# Bluetooth.net
KiCad netlist of a schematic drawn in Altium Designer
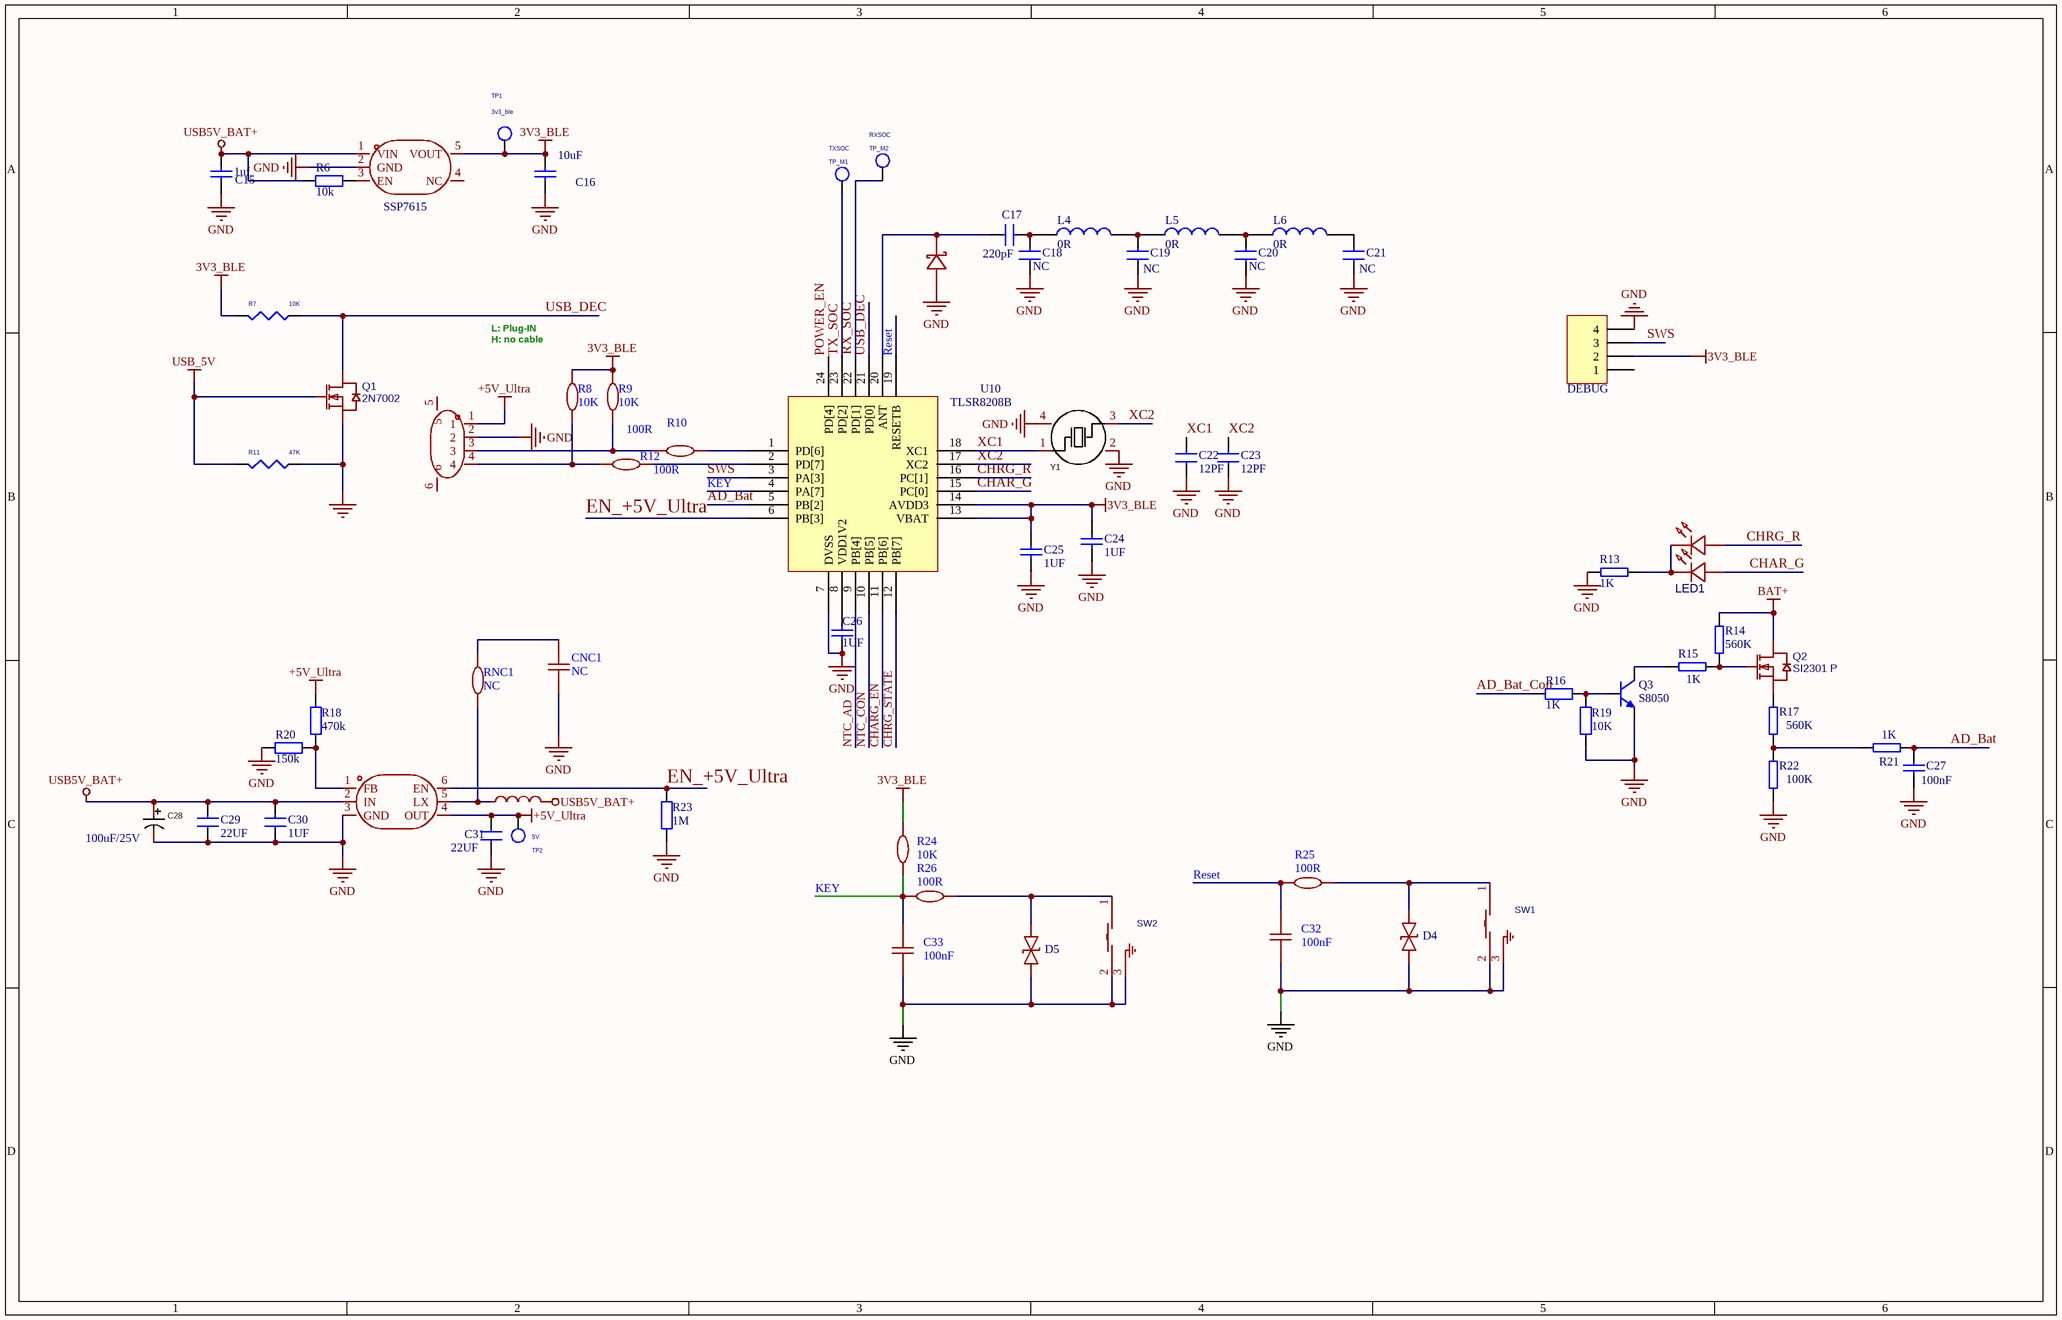
[diagram p0: Bluetooth.SchDoc]

(export (version "E")
  (design (tool "Eeschema 10.0.6"))
  (components
    (comp (ref "C15")
      (value "1uf")
      (footprint "0603_C")
      (description "无极电容")
      (libsource (lib "电容电阻电感保险") (part "Cap1"))
    )
    (comp (ref "C16")
      (value "10uF")
      (footprint "0603_C")
      (description "Capacitor")
      (fields (field (name "PUBLISHER") "Altium Limited"))
      (libsource (lib "*") (part "Cap"))
    )
    (comp (ref "C17")
      (value "220pF")
      (footprint "0402_c")
      (description "Capacitor")
      (libsource (lib "*") (part "CAP"))
    )
    (comp (ref "C18")
      (value "NC")
      (footprint "0402_C")
      (description "Capacitor")
      (libsource (lib "*") (part "CAP"))
    )
    (comp (ref "C19")
      (value "NC")
      (footprint "0402_C")
      (description "Capacitor")
      (libsource (lib "*") (part "CAP"))
    )
    (comp (ref "C20")
      (value "NC")
      (footprint "0402_C")
      (description "Capacitor")
      (libsource (lib "*") (part "CAP"))
    )
    (comp (ref "C21")
      (value "NC")
      (footprint "0402_C")
      (description "Capacitor")
      (libsource (lib "*") (part "CAP"))
    )
    (comp (ref "C22")
      (value "12PF")
      (footprint "0603_c")
      (description "Capacitor")
      (libsource (lib "*") (part "CAP"))
    )
    (comp (ref "C23")
      (value "12PF")
      (footprint "0603_c")
      (description "Capacitor")
      (libsource (lib "*") (part "CAP"))
    )
    (comp (ref "C24") (value "1UF") (footprint "0603_c") (libsource (lib "DIY") (part "CAP")))
    (comp (ref "C25") (value "1UF") (footprint "0603_c") (libsource (lib "DIY") (part "CAP")))
    (comp (ref "C26") (value "1UF") (footprint "0603_c") (libsource (lib "DIY") (part "CAP")))
    (comp (ref "C27") (value "100nF") (footprint "c0402") (libsource (lib "DIY") (part "CAP")))
    (comp (ref "C28")
      (value "100uF/25V")
      (footprint "SMD 6.3*5.4 电解")
      (fields (field (name "MANUFACTURER PART") "RVT1A221M0605"))
      (libsource (lib "altium-import") (part "root_0_RVT1A221M0605_C72494_"))
    )
    (comp (ref "C29")
      (value "22UF")
      (footprint "0805_c")
      (description "Capacitor")
      (libsource (lib "*") (part "CAP"))
    )
    (comp (ref "C30")
      (value "1UF")
      (footprint "0402_c")
      (description "Capacitor")
      (libsource (lib "*") (part "CAP"))
    )
    (comp (ref "C31")
      (value "22UF")
      (footprint "0805_c")
      (description "Capacitor")
      (libsource (lib "*") (part "CAP"))
    )
    (comp (ref "C32")
      (value "100nF")
      (footprint "c0402")
      (libsource (lib "altium-import") (part "root_1_CAP_0603_"))
    )
    (comp (ref "C33")
      (value "100nF")
      (footprint "c0402")
      (libsource (lib "altium-import") (part "root_1_CAP_0603_"))
    )
    (comp (ref "CNC1")
      (value "NC")
      (footprint "c0402")
      (libsource (lib "altium-import") (part "root_1_mirrored_CAP_0603_"))
    )
    (comp (ref "CON4")
      (value "Ultra")
      (footprint "CONN-SMD_4P-P1.25_LT")
      (libsource (lib "altium-import") (part "root_0_mirrored_HC-1.25-4PLT_"))
    )
    (comp (ref "D3")
      (value "SE6V3LHN102T 6.3v单向")
      (footprint "0402-D")
      (libsource (lib "altium-import") (part "root_3_TPNSR05F20NXT5G_"))
    )
    (comp (ref "D4")
      (value "LESD5Z5.0CT1G")
      (footprint "SOD-523_L1.2-W0.8-LS1.6-BI")
      (libsource (lib "altium-import") (part "root_1_LESD5Z5.0CT1G_"))
    )
    (comp (ref "D5")
      (value "LESD5Z5.0CT1G")
      (footprint "SOD-523_L1.2-W0.8-LS1.6-BI")
      (libsource (lib "altium-import") (part "root_1_LESD5Z5.0CT1G_"))
    )
    (comp (ref "L4") (value "0R") (footprint "0402_R") (libsource (lib "*") (part "INDUCTOR")))
    (comp (ref "L5") (value "0R") (footprint "0402_R") (libsource (lib "*") (part "INDUCTOR")))
    (comp (ref "L6") (value "0R") (footprint "0402_R") (libsource (lib "*") (part "INDUCTOR")))
    (comp (ref "L7")
      (value "SLW3012P1R5MST SMD3.0*3.0")
      (footprint "IND-SMD_L3.0-W3.0")
      (libsource (lib "altium-import") (part "root_0_SLW3012P1R5MST_"))
    )
    (comp (ref "LED1")
      (value "*")
      (footprint "LED-SMD_4P-L3.2-W1.6-TL_XL-3216SURUGC")
      (libsource (lib "altium-import") (part "root_0_TJ-S2012SW8TCGLC2R2G-A5_"))
    )
    (comp (ref "P1")
      (value "DEBUG")
      (footprint "SIP4-2.54")
      (description "Header, 4-Pin")
      (fields (field (name "PUBLISHER") "Altium Limited"))
      (libsource (lib "Miscellaneous Connectors") (part "Header 4"))
    )
    (comp (ref "Q1")
      (value "2N7002")
      (footprint "SOT-23")
      (fields
        (field (name "BOM_SUPPLIER PART") "C2890442")
        (field (name "BOM_MANUFACTURER PART") "JMTL3400A")
        (field (name "CONTRIBUTOR") "LCSC")
      )
      (libsource (lib "altium-import") (part "root_0_JMTL3400A_"))
    )
    (comp (ref "Q2")
      (value "SI2301 P")
      (footprint "SOT-23")
      (fields
        (field (name "BOM_SUPPLIER PART") "C2890442")
        (field (name "BOM_MANUFACTURER PART") "JMTL3400A")
        (field (name "CONTRIBUTOR") "LCSC")
      )
      (libsource (lib "") (part "root_0_JMTL3400A__1"))
    )
    (comp (ref "Q3")
      (value "S8050")
      (footprint "SOT-23(SOT-23-3)")
      (description "NPN三极管")
      (libsource (lib "二三极管mos可控硅") (part "NPN_sot23"))
    )
    (comp (ref "R6")
      (value "10k")
      (footprint "R0402")
      (description "Resistor")
      (fields (field (name "PUBLISHER") "Altium Limited"))
      (libsource (lib "") (part "Res2_1"))
    )
    (comp (ref "R7") (value "10K") (footprint "R0402") (libsource (lib "*") (part "R_Dup2")))
    (comp (ref "R8")
      (value "10K")
      (footprint "R0402")
      (libsource (lib "altium-import") (part "root_3_Res_0603_"))
    )
    (comp (ref "R9")
      (value "10K")
      (footprint "R0402")
      (libsource (lib "altium-import") (part "root_3_Res_0603_"))
    )
    (comp (ref "R10")
      (value "100R")
      (footprint "R0402")
      (libsource (lib "altium-import") (part "root_2_Res_0603_"))
    )
    (comp (ref "R11") (value "47K") (footprint "R0402") (libsource (lib "*") (part "R_Dup2")))
    (comp (ref "R12")
      (value "100R")
      (footprint "R0402")
      (libsource (lib "altium-import") (part "root_2_Res_0603_"))
    )
    (comp (ref "R13") (value "1K") (footprint "0603_R") (libsource (lib "DIY") (part "RES")))
    (comp (ref "R14") (value "560K") (footprint "R0402") (libsource (lib "") (part "RES_1")))
    (comp (ref "R15") (value "1K") (footprint "R0402") (libsource (lib "*") (part "RES")))
    (comp (ref "R16")
      (value "1K")
      (footprint "R0402")
      (description "Resistor")
      (fields (field (name "PUBLISHER") "Altium Limited"))
      (libsource (lib "") (part "Res2_3"))
    )
    (comp (ref "R17") (value "560K") (footprint "R0402") (libsource (lib "DIY") (part "RES")))
    (comp (ref "R18")
      (value "470k")
      (footprint "0402_r")
      (description "Resistor")
      (fields (field (name "PUBLISHER") "Altium Limited"))
      (libsource (lib "*") (part "Res2"))
    )
    (comp (ref "R19")
      (value "10K")
      (footprint "R0402")
      (description "Resistor")
      (fields (field (name "PUBLISHER") "Altium Limited"))
      (libsource (lib "") (part "Res2_1"))
    )
    (comp (ref "R20")
      (value "150k")
      (footprint "0402_r")
      (description "Resistor")
      (fields (field (name "PUBLISHER") "Altium Limited"))
      (libsource (lib "") (part "Res2_2"))
    )
    (comp (ref "R21") (value "1K") (footprint "R0402") (libsource (lib "DIY") (part "RES")))
    (comp (ref "R22") (value "100K") (footprint "R0402") (libsource (lib "DIY") (part "RES")))
    (comp (ref "R23")
      (value "1M")
      (footprint "0402_r")
      (description "Resistor")
      (fields (field (name "PUBLISHER") "Altium Limited"))
      (libsource (lib "*") (part "Res2"))
    )
    (comp (ref "R24")
      (value "10K")
      (footprint "R0402")
      (libsource (lib "altium-import") (part "root_1_Res_0603_"))
    )
    (comp (ref "R25")
      (value "100R")
      (footprint "R0402")
      (libsource (lib "altium-import") (part "root_2_Res_0603_"))
    )
    (comp (ref "R26")
      (value "100R")
      (footprint "R0402")
      (libsource (lib "altium-import") (part "root_2_Res_0603_"))
    )
    (comp (ref "RNC1")
      (value "NC")
      (footprint "R0402")
      (libsource (lib "altium-import") (part "root_3_Res_0603_"))
    )
    (comp (ref "SW1")
      (value "Reset")
      (footprint "SMD-KEY-3")
      (libsource (lib "altium-import") (part "root_1_K2-1109SE-I4SW-04_"))
    )
    (comp (ref "SW2")
      (value "OnOff")
      (footprint "SMD-KEY-3")
      (libsource (lib "altium-import") (part "root_1_K2-1109SE-I4SW-04_"))
    )
    (comp (ref "TP1") (value "3v3_ble") (footprint "TP") (libsource (lib "*") (part "T POINT R")))
    (comp (ref "TP2") (value "5V") (footprint "TP") (libsource (lib "*") (part "T POINT R")))
    (comp (ref "TP_M1") (value "TXSOC") (footprint "TP") (libsource (lib "*") (part "T POINT R")))
    (comp (ref "TP_M2") (value "RXSOC") (footprint "TP") (libsource (lib "*") (part "T POINT R")))
    (comp (ref "U2")
      (value "SSP7615")
      (footprint "SOT-23-5")
      (libsource (lib "altium-import") (part "root_0_SSP7615-33M5R_"))
    )
    (comp (ref "U3")
      (value "SY7069ADC")
      (footprint "SOT-23-6")
      (libsource (lib "altium-import") (part "root_0_SY7069ADC_"))
    )
    (comp (ref "U10")
      (value "TLSR8208B")
      (footprint "QFN-24-EP(4*4)")
      (libsource (lib "MyLib") (part "TLSR8208B"))
    )
    (comp (ref "Y1")
      (value "24MHz +-20PPM")
      (footprint "CRYSTAL-SMD_4P-L3.2-W2.5")
      (fields (field (name "MANUFACTURER PART") "TAXM13.56M4RLBCCT2T"))
      (libsource (lib "altium-import") (part "root_0_TAXM13.56M4RLBCCT2T_"))
    )
  )
  (nets
    (net (code "1") (name "+5V_Ultra") (class "Default")
      (node (ref "C31") (pin "2") (pinfunction "2_2") (pintype "passive"))
      (node (ref "CON4") (pin "1") (pinfunction "1_1") (pintype "passive"))
      (node (ref "R18") (pin "2") (pinfunction "2_2") (pintype "passive"))
      (node (ref "TP2") (pin "1") (pinfunction "TP_1") (pintype "passive"))
      (node (ref "U3") (pin "4") (pinfunction "OUT_4") (pintype "passive"))
    )
    (net (code "2") (name "/AD_Bat") (class "Default")
      (node (ref "C27") (pin "2") (pintype "passive"))
      (node (ref "R21") (pin "1") (pinfunction "1_1") (pintype "passive"))
      (node (ref "U10") (pin "5") (pinfunction "PB[2]_5") (pintype "passive"))
    )
    (net (code "3") (name "/AD_Bat_Con") (class "Default")
      (node (ref "R16") (pin "2") (pinfunction "2_2") (pintype "passive"))
    )
    (net (code "4") (name "/CHARG_EN") (class "Default")
      (node (ref "U10") (pin "11") (pinfunction "PB[6]_11") (pintype "passive"))
    )
    (net (code "5") (name "/CHAR_G") (class "Default")
      (node (ref "LED1") (pin "3") (pinfunction "A_3") (pintype "passive"))
      (node (ref "U10") (pin "15") (pinfunction "PC[0]_15") (pintype "passive"))
    )
    (net (code "6") (name "/CHRG_R") (class "Default")
      (node (ref "LED1") (pin "1") (pinfunction "A_1") (pintype "passive"))
      (node (ref "U10") (pin "16") (pinfunction "PC[1]_16") (pintype "passive"))
    )
    (net (code "7") (name "/CHRG_STATE") (class "Default")
      (node (ref "U10") (pin "12") (pinfunction "PB[7]_12") (pintype "passive"))
    )
    (net (code "8") (name "/EN_+5V_Ultra") (class "Default")
      (node (ref "R23") (pin "2") (pinfunction "2_2") (pintype "passive"))
      (node (ref "U10") (pin "6") (pinfunction "PB[3]_6") (pintype "passive"))
      (node (ref "U3") (pin "6") (pinfunction "EN_6") (pintype "passive"))
    )
    (net (code "9") (name "/KEY") (class "Default")
      (node (ref "C33") (pin "2") (pinfunction "2_2") (pintype "passive"))
      (node (ref "R24") (pin "1") (pinfunction "1_1") (pintype "passive"))
      (node (ref "R26") (pin "2") (pinfunction "2_2") (pintype "passive"))
      (node (ref "U10") (pin "4") (pinfunction "PA[7]_4") (pintype "passive"))
    )
    (net (code "10") (name "/NTC_AD") (class "Default")
      (node (ref "U10") (pin "9") (pinfunction "PB[4]_9") (pintype "passive"))
    )
    (net (code "11") (name "/NTC_CON") (class "Default")
      (node (ref "U10") (pin "10") (pinfunction "PB[5]_10") (pintype "passive"))
    )
    (net (code "12") (name "/POWER_EN") (class "Default")
      (node (ref "U10") (pin "24") (pinfunction "PD[4]_24") (pintype "passive"))
    )
    (net (code "13") (name "/RX_SOC") (class "Default")
      (node (ref "TP_M2") (pin "1") (pinfunction "TP_1") (pintype "passive"))
      (node (ref "U10") (pin "22") (pinfunction "PD[1]_22") (pintype "passive"))
    )
    (net (code "14") (name "/Reset") (class "Default")
      (node (ref "C32") (pin "2") (pinfunction "2_2") (pintype "passive"))
      (node (ref "R25") (pin "2") (pinfunction "2_2") (pintype "passive"))
      (node (ref "U10") (pin "19") (pinfunction "RESETB_19") (pintype "passive"))
    )
    (net (code "15") (name "/SWS") (class "Default")
      (node (ref "P1") (pin "3") (pinfunction "3_3") (pintype "passive"))
      (node (ref "U10") (pin "3") (pinfunction "PA[3]_3") (pintype "passive"))
    )
    (net (code "16") (name "/TX_SOC") (class "Default")
      (node (ref "TP_M1") (pin "1") (pinfunction "TP_1") (pintype "passive"))
      (node (ref "U10") (pin "23") (pinfunction "PD[2]_23") (pintype "passive"))
    )
    (net (code "17") (name "/USB_DEC") (class "Default")
      (node (ref "Q1") (pin "3") (pinfunction "D_3") (pintype "passive"))
      (node (ref "R7") (pin "2") (pinfunction "2_2") (pintype "passive"))
      (node (ref "U10") (pin "21") (pinfunction "PD[0]_21") (pintype "passive"))
    )
    (net (code "18") (name "/XC1") (class "Default")
      (node (ref "C22") (pin "2") (pinfunction "2_2") (pintype "passive"))
      (node (ref "U10") (pin "18") (pinfunction "XC1_18") (pintype "passive"))
      (node (ref "Y1") (pin "1") (pinfunction "OSC1_1") (pintype "passive"))
    )
    (net (code "19") (name "/XC2") (class "Default")
      (node (ref "C23") (pin "2") (pinfunction "2_2") (pintype "passive"))
      (node (ref "U10") (pin "17") (pinfunction "XC2_17") (pintype "passive"))
      (node (ref "Y1") (pin "3") (pinfunction "OSC2_3") (pintype "passive"))
    )
    (net (code "20") (name "3V3_BLE") (class "Default")
      (node (ref "C16") (pin "2") (pinfunction "2_2") (pintype "passive"))
      (node (ref "C24") (pin "1") (pintype "passive"))
      (node (ref "C25") (pin "1") (pintype "passive"))
      (node (ref "P1") (pin "2") (pinfunction "2_2") (pintype "passive"))
      (node (ref "R24") (pin "2") (pinfunction "2_2") (pintype "passive"))
      (node (ref "R7") (pin "1") (pinfunction "1_1") (pintype "passive"))
      (node (ref "R8") (pin "1") (pinfunction "1_1") (pintype "passive"))
      (node (ref "R9") (pin "1") (pinfunction "1_1") (pintype "passive"))
      (node (ref "TP1") (pin "1") (pinfunction "TP_1") (pintype "passive"))
      (node (ref "U10") (pin "13") (pinfunction "VBAT_13") (pintype "passive"))
      (node (ref "U10") (pin "14") (pinfunction "AVDD3_14") (pintype "passive"))
      (node (ref "U2") (pin "5") (pinfunction "VOUT_5") (pintype "passive"))
    )
    (net (code "21") (name "BAT+") (class "Default")
      (node (ref "Q2") (pin "2") (pinfunction "D_2") (pintype "passive"))
      (node (ref "R14") (pin "1") (pintype "passive"))
    )
    (net (code "22") (name "GND") (class "Default")
      (node (ref "C15") (pin "1") (pinfunction "1_1") (pintype "passive"))
      (node (ref "C16") (pin "1") (pinfunction "1_1") (pintype "passive"))
      (node (ref "C18") (pin "1") (pinfunction "1_1") (pintype "passive"))
      (node (ref "C19") (pin "1") (pinfunction "1_1") (pintype "passive"))
      (node (ref "C20") (pin "1") (pinfunction "1_1") (pintype "passive"))
      (node (ref "C21") (pin "1") (pinfunction "1_1") (pintype "passive"))
      (node (ref "C22") (pin "1") (pinfunction "1_1") (pintype "passive"))
      (node (ref "C23") (pin "1") (pinfunction "1_1") (pintype "passive"))
      (node (ref "C24") (pin "2") (pintype "passive"))
      (node (ref "C25") (pin "2") (pintype "passive"))
      (node (ref "C26") (pin "1") (pintype "passive"))
      (node (ref "C27") (pin "1") (pintype "passive"))
      (node (ref "C28") (pin "2") (pinfunction "2_2") (pintype "passive"))
      (node (ref "C29") (pin "1") (pinfunction "1_1") (pintype "passive"))
      (node (ref "C30") (pin "1") (pinfunction "1_1") (pintype "passive"))
      (node (ref "C31") (pin "1") (pinfunction "1_1") (pintype "passive"))
      (node (ref "C32") (pin "1") (pinfunction "1_1") (pintype "passive"))
      (node (ref "C33") (pin "1") (pinfunction "1_1") (pintype "passive"))
      (node (ref "CNC1") (pin "1") (pinfunction "1_1") (pintype "passive"))
      (node (ref "CON4") (pin "2") (pinfunction "2_2") (pintype "passive"))
      (node (ref "D3") (pin "2") (pinfunction "A_2") (pintype "passive"))
      (node (ref "D4") (pin "1") (pinfunction "1_1") (pintype "passive"))
      (node (ref "D5") (pin "1") (pinfunction "1_1") (pintype "passive"))
      (node (ref "P1") (pin "4") (pinfunction "4_4") (pintype "passive"))
      (node (ref "Q1") (pin "2") (pinfunction "S_2") (pintype "passive"))
      (node (ref "Q3") (pin "2") (pinfunction "E_2") (pintype "passive"))
      (node (ref "R11") (pin "2") (pinfunction "2_2") (pintype "passive"))
      (node (ref "R13") (pin "1") (pinfunction "1_1") (pintype "passive"))
      (node (ref "R19") (pin "1") (pinfunction "1_1") (pintype "passive"))
      (node (ref "R20") (pin "2") (pinfunction "2_2") (pintype "passive"))
      (node (ref "R22") (pin "2") (pinfunction "2_2") (pintype "passive"))
      (node (ref "R23") (pin "1") (pinfunction "1_1") (pintype "passive"))
      (node (ref "SW1") (pin "2") (pinfunction "2_2") (pintype "passive"))
      (node (ref "SW1") (pin "3") (pinfunction "3_3") (pintype "passive"))
      (node (ref "SW2") (pin "2") (pinfunction "2_2") (pintype "passive"))
      (node (ref "SW2") (pin "3") (pinfunction "3_3") (pintype "passive"))
      (node (ref "U10") (pin "7") (pinfunction "DVSS_7") (pintype "passive"))
      (node (ref "U2") (pin "2") (pinfunction "GND_2") (pintype "passive"))
      (node (ref "U3") (pin "3") (pinfunction "GND_3") (pintype "passive"))
      (node (ref "Y1") (pin "2") (pinfunction "GND_2") (pintype "passive"))
      (node (ref "Y1") (pin "4") (pinfunction "GND_4") (pintype "passive"))
    )
    (net (code "23") (name "Net-(C17-Pad2)") (class "Default")
      (node (ref "C17") (pin "2") (pinfunction "2_2") (pintype "passive"))
      (node (ref "C18") (pin "2") (pinfunction "2_2") (pintype "passive"))
      (node (ref "L4") (pin "1") (pinfunction "1_1") (pintype "passive"))
    )
    (net (code "24") (name "Net-(C19-Pad2)") (class "Default")
      (node (ref "C19") (pin "2") (pinfunction "2_2") (pintype "passive"))
      (node (ref "L4") (pin "2") (pinfunction "2_2") (pintype "passive"))
      (node (ref "L5") (pin "1") (pinfunction "1_1") (pintype "passive"))
    )
    (net (code "25") (name "Net-(C20-Pad2)") (class "Default")
      (node (ref "C20") (pin "2") (pinfunction "2_2") (pintype "passive"))
      (node (ref "L5") (pin "2") (pinfunction "2_2") (pintype "passive"))
      (node (ref "L6") (pin "1") (pinfunction "1_1") (pintype "passive"))
    )
    (net (code "26") (name "Net-(C21-Pad2)") (class "Default")
      (node (ref "C21") (pin "2") (pinfunction "2_2") (pintype "passive"))
      (node (ref "L6") (pin "2") (pinfunction "2_2") (pintype "passive"))
    )
    (net (code "27") (name "Net-(CNC1-Pad2)") (class "Default")
      (node (ref "CNC1") (pin "2") (pinfunction "2_2") (pintype "passive"))
      (node (ref "RNC1") (pin "1") (pinfunction "1_1") (pintype "passive"))
    )
    (net (code "28") (name "Net-(CON4-Pad3)") (class "Default")
      (node (ref "CON4") (pin "3") (pinfunction "3_3") (pintype "passive"))
      (node (ref "R10") (pin "2") (pinfunction "2_2") (pintype "passive"))
      (node (ref "R9") (pin "2") (pinfunction "2_2") (pintype "passive"))
    )
    (net (code "29") (name "Net-(CON4-Pad4)") (class "Default")
      (node (ref "CON4") (pin "4") (pinfunction "4_4") (pintype "passive"))
      (node (ref "R12") (pin "2") (pinfunction "2_2") (pintype "passive"))
      (node (ref "R8") (pin "2") (pinfunction "2_2") (pintype "passive"))
    )
    (net (code "30") (name "Net-(D3-C)") (class "Default")
      (node (ref "C17") (pin "1") (pinfunction "1_1") (pintype "passive"))
      (node (ref "D3") (pin "1") (pinfunction "C_1") (pintype "passive"))
      (node (ref "U10") (pin "20") (pinfunction "ANT_20") (pintype "passive"))
    )
    (net (code "31") (name "Net-(D4-Pad2)") (class "Default")
      (node (ref "D4") (pin "2") (pinfunction "2_2") (pintype "passive"))
      (node (ref "R25") (pin "1") (pinfunction "1_1") (pintype "passive"))
      (node (ref "SW1") (pin "1") (pinfunction "1_1") (pintype "passive"))
    )
    (net (code "32") (name "Net-(D5-Pad2)") (class "Default")
      (node (ref "D5") (pin "2") (pinfunction "2_2") (pintype "passive"))
      (node (ref "R26") (pin "1") (pinfunction "1_1") (pintype "passive"))
      (node (ref "SW2") (pin "1") (pinfunction "1_1") (pintype "passive"))
    )
    (net (code "33") (name "Net-(LED1-K-Pad2)") (class "Default")
      (node (ref "LED1") (pin "2") (pinfunction "K_2") (pintype "passive"))
      (node (ref "LED1") (pin "4") (pinfunction "K_4") (pintype "passive"))
      (node (ref "R13") (pin "2") (pinfunction "2_2") (pintype "passive"))
    )
    (net (code "34") (name "Net-(Q2-G)") (class "Default")
      (node (ref "Q2") (pin "1") (pinfunction "G_1") (pintype "passive"))
      (node (ref "R14") (pin "2") (pintype "passive"))
      (node (ref "R15") (pin "1") (pintype "passive"))
    )
    (net (code "35") (name "Net-(Q2-S)") (class "Default")
      (node (ref "Q2") (pin "3") (pinfunction "S_3") (pintype "passive"))
      (node (ref "R17") (pin "1") (pinfunction "1_1") (pintype "passive"))
    )
    (net (code "36") (name "Net-(Q3-B)") (class "Default")
      (node (ref "Q3") (pin "1") (pinfunction "B_1") (pintype "passive"))
      (node (ref "R16") (pin "1") (pinfunction "1_1") (pintype "passive"))
      (node (ref "R19") (pin "2") (pinfunction "2_2") (pintype "passive"))
    )
    (net (code "37") (name "Net-(Q3-C)") (class "Default")
      (node (ref "Q3") (pin "3") (pinfunction "C_3") (pintype "passive"))
      (node (ref "R15") (pin "2") (pintype "passive"))
    )
    (net (code "38") (name "Net-(R17-Pad2)") (class "Default")
      (node (ref "R17") (pin "2") (pinfunction "2_2") (pintype "passive"))
      (node (ref "R21") (pin "2") (pinfunction "2_2") (pintype "passive"))
      (node (ref "R22") (pin "1") (pinfunction "1_1") (pintype "passive"))
    )
    (net (code "39") (name "Net-(U2-EN)") (class "Default")
      (node (ref "R6") (pin "2") (pinfunction "2_2") (pintype "passive"))
      (node (ref "U2") (pin "3") (pinfunction "EN_3") (pintype "passive"))
    )
    (net (code "40") (name "Net-(U3-FB)") (class "Default")
      (node (ref "R18") (pin "1") (pinfunction "1_1") (pintype "passive"))
      (node (ref "R20") (pin "1") (pinfunction "1_1") (pintype "passive"))
      (node (ref "U3") (pin "1") (pinfunction "FB_1") (pintype "passive"))
    )
    (net (code "41") (name "Net-(U3-LX)") (class "Default")
      (node (ref "L7") (pin "1") (pinfunction "1_1") (pintype "passive"))
      (node (ref "RNC1") (pin "2") (pinfunction "2_2") (pintype "passive"))
      (node (ref "U3") (pin "5") (pinfunction "LX_5") (pintype "passive"))
    )
    (net (code "42") (name "Net-(U10-PD[6])") (class "Default")
      (node (ref "R10") (pin "1") (pinfunction "1_1") (pintype "passive"))
      (node (ref "U10") (pin "1") (pinfunction "PD[6]_1") (pintype "passive"))
    )
    (net (code "43") (name "Net-(U10-PD[7])") (class "Default")
      (node (ref "R12") (pin "1") (pinfunction "1_1") (pintype "passive"))
      (node (ref "U10") (pin "2") (pinfunction "PD[7]_2") (pintype "passive"))
    )
    (net (code "44") (name "Net-(U10-VDD1V2)") (class "Default")
      (node (ref "C26") (pin "2") (pintype "passive"))
      (node (ref "U10") (pin "8") (pinfunction "VDD1V2_8") (pintype "passive"))
    )
    (net (code "45") (name "USB5V_BAT+") (class "Default")
      (node (ref "C15") (pin "2") (pinfunction "2_2") (pintype "passive"))
      (node (ref "C28") (pin "1") (pinfunction "1_1") (pintype "passive"))
      (node (ref "C29") (pin "2") (pinfunction "2_2") (pintype "passive"))
      (node (ref "C30") (pin "2") (pinfunction "2_2") (pintype "passive"))
      (node (ref "L7") (pin "2") (pinfunction "2_2") (pintype "passive"))
      (node (ref "R6") (pin "1") (pinfunction "1_1") (pintype "passive"))
      (node (ref "U2") (pin "1") (pinfunction "VIN_1") (pintype "passive"))
      (node (ref "U3") (pin "2") (pinfunction "IN_2") (pintype "passive"))
    )
    (net (code "46") (name "USB_5V") (class "Default")
      (node (ref "Q1") (pin "1") (pinfunction "G_1") (pintype "passive"))
      (node (ref "R11") (pin "1") (pinfunction "1_1") (pintype "passive"))
    )
    (net (code "47") (name "unconnected-(CON4-Pad5)") (class "Default")
      (node (ref "CON4") (pin "5") (pinfunction "5_5") (pintype "passive"))
    )
    (net (code "48") (name "unconnected-(CON4-Pad6)") (class "Default")
      (node (ref "CON4") (pin "6") (pinfunction "6_6") (pintype "passive"))
    )
    (net (code "49") (name "unconnected-(P1-Pad1)") (class "Default")
      (node (ref "P1") (pin "1") (pinfunction "1_1") (pintype "passive"))
    )
    (net (code "50") (name "unconnected-(U2-NC-Pad4)") (class "Default")
      (node (ref "U2") (pin "4") (pinfunction "NC_4") (pintype "passive"))
    )
  )
)
